# RK3399_USB2_TYPEC_USIC.net
KiCad netlist of a schematic drawn in Altium Designer
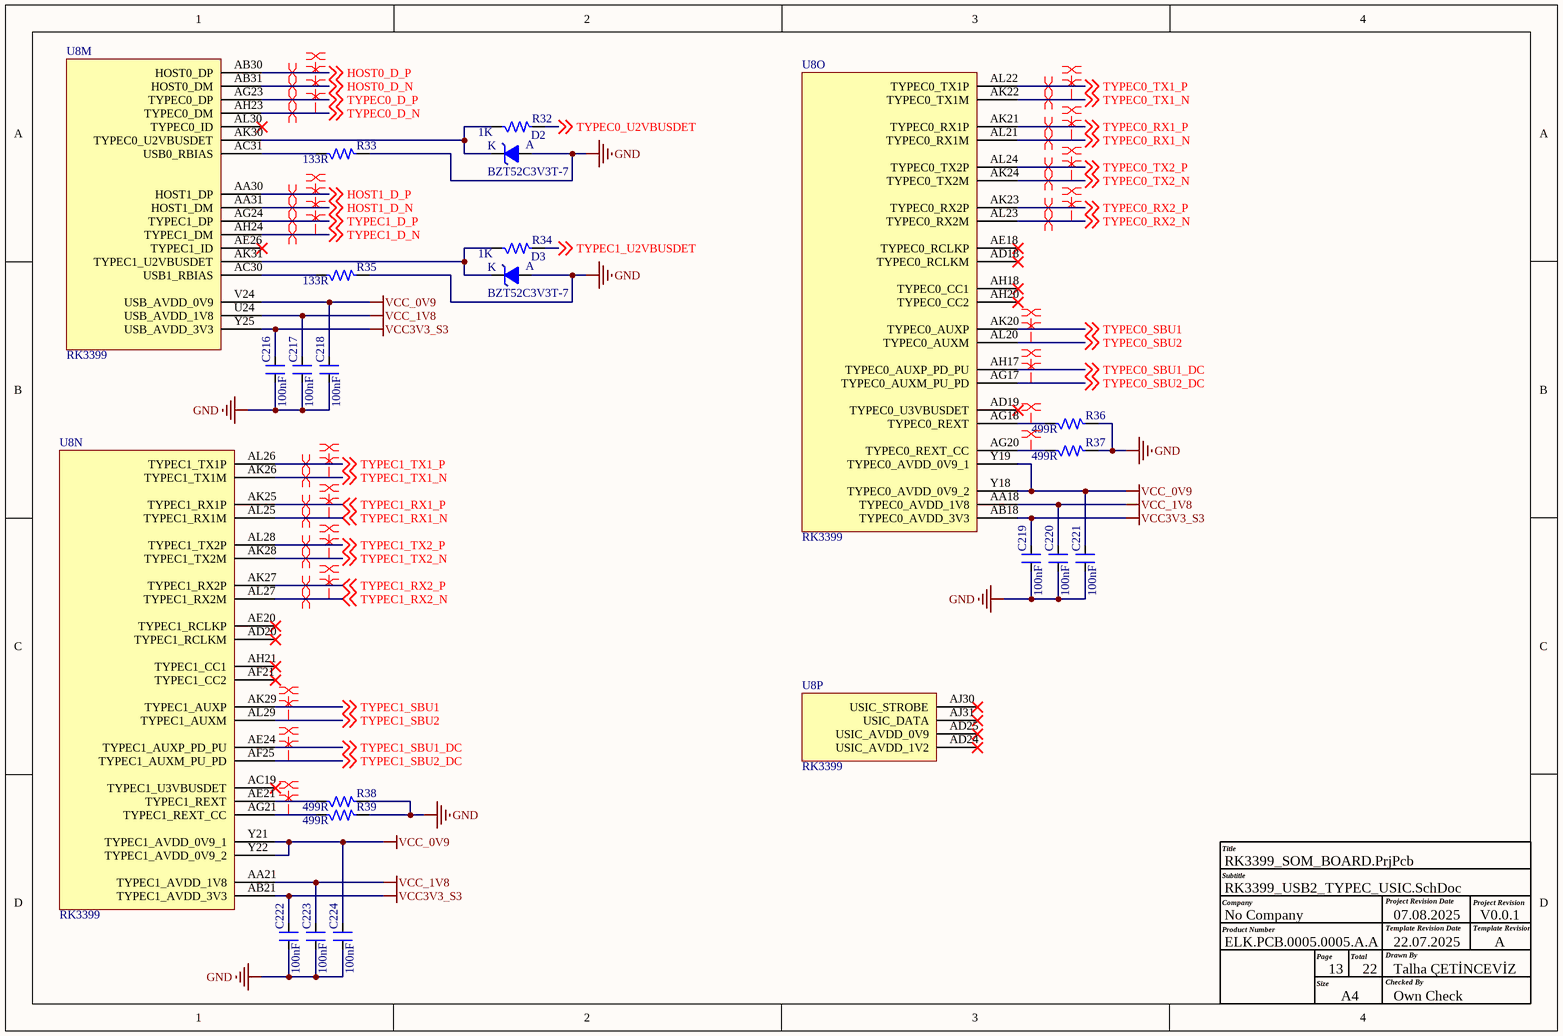
[diagram p0: RK3399_USB2_TYPEC_USIC.SchDoc]

(export (version "E")
  (design (tool "Eeschema 10.0.6"))
  (components
    (comp (ref "C216")
      (value "100nF")
      (footprint "CAP_0201")
      (description "0.1µF ±10% 25V Ceramic Capacitor X5R 0201 (0603 Metric)")
      (fields
        (field (name "MANUFACTURER") "TDK Corporation")
        (field (name "MANUFACTURER PART NUMBER") "C0603X5R1E104K030BB")
      )
      (libsource (lib "EsteemPCB_SOM_Course_intlib") (part "CAP_100nF-25V-10%-0201"))
    )
    (comp (ref "C217")
      (value "100nF")
      (footprint "CAP_0201")
      (description "0.1µF ±10% 25V Ceramic Capacitor X5R 0201 (0603 Metric)")
      (fields
        (field (name "MANUFACTURER") "TDK Corporation")
        (field (name "MANUFACTURER PART NUMBER") "C0603X5R1E104K030BB")
      )
      (libsource (lib "EsteemPCB_SOM_Course_intlib") (part "CAP_100nF-25V-10%-0201"))
    )
    (comp (ref "C218")
      (value "100nF")
      (footprint "CAP_0201")
      (description "0.1µF ±10% 25V Ceramic Capacitor X5R 0201 (0603 Metric)")
      (fields
        (field (name "MANUFACTURER") "TDK Corporation")
        (field (name "MANUFACTURER PART NUMBER") "C0603X5R1E104K030BB")
      )
      (libsource (lib "EsteemPCB_SOM_Course_intlib") (part "CAP_100nF-25V-10%-0201"))
    )
    (comp (ref "C219")
      (value "100nF")
      (footprint "CAP_0201")
      (description "0.1µF ±10% 25V Ceramic Capacitor X5R 0201 (0603 Metric)")
      (fields
        (field (name "MANUFACTURER") "TDK Corporation")
        (field (name "MANUFACTURER PART NUMBER") "C0603X5R1E104K030BB")
      )
      (libsource (lib "EsteemPCB_SOM_Course_intlib") (part "CAP_100nF-25V-10%-0201"))
    )
    (comp (ref "C220")
      (value "100nF")
      (footprint "CAP_0201")
      (description "0.1µF ±10% 25V Ceramic Capacitor X5R 0201 (0603 Metric)")
      (fields
        (field (name "MANUFACTURER") "TDK Corporation")
        (field (name "MANUFACTURER PART NUMBER") "C0603X5R1E104K030BB")
      )
      (libsource (lib "EsteemPCB_SOM_Course_intlib") (part "CAP_100nF-25V-10%-0201"))
    )
    (comp (ref "C221")
      (value "100nF")
      (footprint "CAP_0201")
      (description "0.1µF ±10% 25V Ceramic Capacitor X5R 0201 (0603 Metric)")
      (fields
        (field (name "MANUFACTURER") "TDK Corporation")
        (field (name "MANUFACTURER PART NUMBER") "C0603X5R1E104K030BB")
      )
      (libsource (lib "EsteemPCB_SOM_Course_intlib") (part "CAP_100nF-25V-10%-0201"))
    )
    (comp (ref "C222")
      (value "100nF")
      (footprint "CAP_0201")
      (description "0.1µF ±10% 25V Ceramic Capacitor X5R 0201 (0603 Metric)")
      (fields
        (field (name "MANUFACTURER") "TDK Corporation")
        (field (name "MANUFACTURER PART NUMBER") "C0603X5R1E104K030BB")
      )
      (libsource (lib "EsteemPCB_SOM_Course_intlib") (part "CAP_100nF-25V-10%-0201"))
    )
    (comp (ref "C223")
      (value "100nF")
      (footprint "CAP_0201")
      (description "0.1µF ±10% 25V Ceramic Capacitor X5R 0201 (0603 Metric)")
      (fields
        (field (name "MANUFACTURER") "TDK Corporation")
        (field (name "MANUFACTURER PART NUMBER") "C0603X5R1E104K030BB")
      )
      (libsource (lib "EsteemPCB_SOM_Course_intlib") (part "CAP_100nF-25V-10%-0201"))
    )
    (comp (ref "C224")
      (value "100nF")
      (footprint "CAP_0201")
      (description "0.1µF ±10% 25V Ceramic Capacitor X5R 0201 (0603 Metric)")
      (fields
        (field (name "MANUFACTURER") "TDK Corporation")
        (field (name "MANUFACTURER PART NUMBER") "C0603X5R1E104K030BB")
      )
      (libsource (lib "EsteemPCB_SOM_Course_intlib") (part "CAP_100nF-25V-10%-0201"))
    )
    (comp (ref "D2")
      (value "BZT52C3V3T-7")
      (footprint "DIO_SOD523")
      (description "Zener Diode 3.3V 300mW ±6% Surface Mount SOD-523")
      (fields (field (name "MANUFACTURER") "Diodes Incorporated"))
      (libsource (lib "EsteemPCB_SOM_Course_intlib") (part "DIO-Z_3.3V-300mW-SOD-523"))
    )
    (comp (ref "D3")
      (value "BZT52C3V3T-7")
      (footprint "DIO_SOD523")
      (description "Zener Diode 3.3V 300mW ±6% Surface Mount SOD-523")
      (fields (field (name "MANUFACTURER") "Diodes Incorporated"))
      (libsource (lib "EsteemPCB_SOM_Course_intlib") (part "DIO-Z_3.3V-300mW-SOD-523"))
    )
    (comp (ref "R32")
      (value "1K")
      (footprint "RES_0201")
      (description "1 kOhms ±1% 0.05W, 1/20W Chip Resistor 0201 (0603 Metric) Thick Film")
      (fields
        (field (name "MANUFACTURER") "Yageo")
        (field (name "MANUFACTURER PART NUMBER") "RC0201FR-071KL")
      )
      (libsource (lib "EsteemPCB_SOM_Course_intlib") (part "RES_1K-0.05W-1%-0201"))
    )
    (comp (ref "R33")
      (value "133R")
      (footprint "RES_0201")
      (description "133 Ohms ±1% 0.05W, 1/20W Chip Resistor 0201 (0603 Metric) Automotive AEC-Q200 Thick Film")
      (fields
        (field (name "MANUFACTURER") "Panasonic Electronic Components")
        (field (name "MANUFACTURER PART NUMBER") "ERJ-1GNF1330C")
      )
      (libsource (lib "EsteemPCB_SOM_Course_intlib") (part "RES_133R-0.05W-1%-0201"))
    )
    (comp (ref "R34")
      (value "1K")
      (footprint "RES_0201")
      (description "1 kOhms ±1% 0.05W, 1/20W Chip Resistor 0201 (0603 Metric) Thick Film")
      (fields
        (field (name "MANUFACTURER") "Yageo")
        (field (name "MANUFACTURER PART NUMBER") "RC0201FR-071KL")
      )
      (libsource (lib "EsteemPCB_SOM_Course_intlib") (part "RES_1K-0.05W-1%-0201"))
    )
    (comp (ref "R35")
      (value "133R")
      (footprint "RES_0201")
      (description "133 Ohms ±1% 0.05W, 1/20W Chip Resistor 0201 (0603 Metric) Automotive AEC-Q200 Thick Film")
      (fields
        (field (name "MANUFACTURER") "Panasonic Electronic Components")
        (field (name "MANUFACTURER PART NUMBER") "ERJ-1GNF1330C")
      )
      (libsource (lib "EsteemPCB_SOM_Course_intlib") (part "RES_133R-0.05W-1%-0201"))
    )
    (comp (ref "R36")
      (value "499R")
      (footprint "RES_0201")
      (description "499 Ohms ±1% 0.05W, 1/20W Chip Resistor 0201 (0603 Metric) Thick Film")
      (fields
        (field (name "MANUFACTURER") "Stackpole Electronics Inc")
        (field (name "MANUFACTURER PART NUMBER") "RMCF0201FT499R")
      )
      (libsource (lib "EsteemPCB_SOM_Course_intlib") (part "RES_499R-0.05W-1%-0201"))
    )
    (comp (ref "R37")
      (value "499R")
      (footprint "RES_0201")
      (description "499 Ohms ±1% 0.05W, 1/20W Chip Resistor 0201 (0603 Metric) Thick Film")
      (fields
        (field (name "MANUFACTURER") "Stackpole Electronics Inc")
        (field (name "MANUFACTURER PART NUMBER") "RMCF0201FT499R")
      )
      (libsource (lib "EsteemPCB_SOM_Course_intlib") (part "RES_499R-0.05W-1%-0201"))
    )
    (comp (ref "R38")
      (value "499R")
      (footprint "RES_0201")
      (description "499 Ohms ±1% 0.05W, 1/20W Chip Resistor 0201 (0603 Metric) Thick Film")
      (fields
        (field (name "MANUFACTURER") "Stackpole Electronics Inc")
        (field (name "MANUFACTURER PART NUMBER") "RMCF0201FT499R")
      )
      (libsource (lib "EsteemPCB_SOM_Course_intlib") (part "RES_499R-0.05W-1%-0201"))
    )
    (comp (ref "R39")
      (value "499R")
      (footprint "RES_0201")
      (description "499 Ohms ±1% 0.05W, 1/20W Chip Resistor 0201 (0603 Metric) Thick Film")
      (fields
        (field (name "MANUFACTURER") "Stackpole Electronics Inc")
        (field (name "MANUFACTURER PART NUMBER") "RMCF0201FT499R")
      )
      (libsource (lib "EsteemPCB_SOM_Course_intlib") (part "RES_499R-0.05W-1%-0201"))
    )
    (comp (ref "U8")
      (value "RK3399")
      (footprint "FBGA828_23_826X826")
      (description "RK3399 is a low power, high performance processor for computing, personal mobile.")
      (fields (field (name "MANUFACTURER") "Rockchip"))
      (libsource (lib "EsteemPCB_SOM_Course_intlib") (part "IC_RK3399-FCBGA828"))
    )
  )
  (nets
    (net (code "1") (name "GND") (class "Default")
      (node (ref "C216") (pin "1") (pinfunction "1_1") (pintype "passive"))
      (node (ref "C217") (pin "1") (pinfunction "1_1") (pintype "passive"))
      (node (ref "C218") (pin "1") (pinfunction "1_1") (pintype "passive"))
      (node (ref "C219") (pin "1") (pinfunction "1_1") (pintype "passive"))
      (node (ref "C220") (pin "1") (pinfunction "1_1") (pintype "passive"))
      (node (ref "C221") (pin "1") (pinfunction "1_1") (pintype "passive"))
      (node (ref "C222") (pin "1") (pinfunction "1_1") (pintype "passive"))
      (node (ref "C223") (pin "1") (pinfunction "1_1") (pintype "passive"))
      (node (ref "C224") (pin "1") (pinfunction "1_1") (pintype "passive"))
      (node (ref "D2") (pin "A") (pinfunction "A_A") (pintype "passive"))
      (node (ref "D3") (pin "A") (pinfunction "A_A") (pintype "passive"))
      (node (ref "R33") (pin "2") (pinfunction "2_2") (pintype "passive"))
      (node (ref "R35") (pin "2") (pinfunction "2_2") (pintype "passive"))
      (node (ref "R36") (pin "2") (pinfunction "2_2") (pintype "passive"))
      (node (ref "R37") (pin "2") (pinfunction "2_2") (pintype "passive"))
      (node (ref "R38") (pin "2") (pinfunction "2_2") (pintype "passive"))
      (node (ref "R39") (pin "2") (pinfunction "2_2") (pintype "passive"))
    )
    (net (code "2") (name "HOST0_D_N") (class "Default")
      (node (ref "U8") (pin "AB31") (pinfunction "HOST0_DM_AB31") (pintype "passive"))
    )
    (net (code "3") (name "HOST0_D_P") (class "Default")
      (node (ref "U8") (pin "AB30") (pinfunction "HOST0_DP_AB30") (pintype "passive"))
    )
    (net (code "4") (name "HOST1_D_N") (class "Default")
      (node (ref "U8") (pin "AA31") (pinfunction "HOST1_DM_AA31") (pintype "passive"))
    )
    (net (code "5") (name "HOST1_D_P") (class "Default")
      (node (ref "U8") (pin "AA30") (pinfunction "HOST1_DP_AA30") (pintype "passive"))
    )
    (net (code "6") (name "Net-(U8M-TYPEC0_U2VBUSDET)") (class "Default")
      (node (ref "D2") (pin "K") (pinfunction "K_K") (pintype "passive"))
      (node (ref "R32") (pin "1") (pinfunction "1_1") (pintype "passive"))
      (node (ref "U8") (pin "AK30") (pinfunction "TYPEC0_U2VBUSDET_AK30") (pintype "passive"))
    )
    (net (code "7") (name "Net-(U8M-TYPEC1_U2VBUSDET)") (class "Default")
      (node (ref "D3") (pin "K") (pinfunction "K_K") (pintype "passive"))
      (node (ref "R34") (pin "1") (pinfunction "1_1") (pintype "passive"))
      (node (ref "U8") (pin "AK31") (pinfunction "TYPEC1_U2VBUSDET_AK31") (pintype "passive"))
    )
    (net (code "8") (name "Net-(U8M-USB0_RBIAS)") (class "Default")
      (node (ref "R33") (pin "1") (pinfunction "1_1") (pintype "passive"))
      (node (ref "U8") (pin "AC31") (pinfunction "USB0_RBIAS_AC31") (pintype "passive"))
    )
    (net (code "9") (name "Net-(U8M-USB1_RBIAS)") (class "Default")
      (node (ref "R35") (pin "1") (pinfunction "1_1") (pintype "passive"))
      (node (ref "U8") (pin "AC30") (pinfunction "USB1_RBIAS_AC30") (pintype "passive"))
    )
    (net (code "10") (name "Net-(U8N-TYPEC1_REXT)") (class "Default")
      (node (ref "R38") (pin "1") (pinfunction "1_1") (pintype "passive"))
      (node (ref "U8") (pin "AE21") (pinfunction "TYPEC1_REXT_AE21") (pintype "passive"))
    )
    (net (code "11") (name "Net-(U8N-TYPEC1_REXT_CC)") (class "Default")
      (node (ref "R39") (pin "1") (pinfunction "1_1") (pintype "passive"))
      (node (ref "U8") (pin "AG21") (pinfunction "TYPEC1_REXT_CC_AG21") (pintype "passive"))
    )
    (net (code "12") (name "Net-(U8O-TYPEC0_REXT)") (class "Default")
      (node (ref "R36") (pin "1") (pinfunction "1_1") (pintype "passive"))
      (node (ref "U8") (pin "AG18") (pinfunction "TYPEC0_REXT_AG18") (pintype "passive"))
    )
    (net (code "13") (name "Net-(U8O-TYPEC0_REXT_CC)") (class "Default")
      (node (ref "R37") (pin "1") (pinfunction "1_1") (pintype "passive"))
      (node (ref "U8") (pin "AG20") (pinfunction "TYPEC0_REXT_CC_AG20") (pintype "passive"))
    )
    (net (code "14") (name "TYPEC0_D_N") (class "Default")
      (node (ref "U8") (pin "AH23") (pinfunction "TYPEC0_DM_AH23") (pintype "passive"))
    )
    (net (code "15") (name "TYPEC0_D_P") (class "Default")
      (node (ref "U8") (pin "AG23") (pinfunction "TYPEC0_DP_AG23") (pintype "passive"))
    )
    (net (code "16") (name "TYPEC0_RX1_N") (class "Default")
      (node (ref "U8") (pin "AL21") (pinfunction "TYPEC0_RX1M_AL21") (pintype "passive"))
    )
    (net (code "17") (name "TYPEC0_RX1_P") (class "Default")
      (node (ref "U8") (pin "AK21") (pinfunction "TYPEC0_RX1P_AK21") (pintype "passive"))
    )
    (net (code "18") (name "TYPEC0_RX2_N") (class "Default")
      (node (ref "U8") (pin "AL23") (pinfunction "TYPEC0_RX2M_AL23") (pintype "passive"))
    )
    (net (code "19") (name "TYPEC0_RX2_P") (class "Default")
      (node (ref "U8") (pin "AK23") (pinfunction "TYPEC0_RX2P_AK23") (pintype "passive"))
    )
    (net (code "20") (name "TYPEC0_SBU1") (class "Default")
      (node (ref "U8") (pin "AK20") (pinfunction "TYPEC0_AUXP_AK20") (pintype "passive"))
    )
    (net (code "21") (name "TYPEC0_SBU1_DC") (class "Default")
      (node (ref "U8") (pin "AH17") (pinfunction "TYPEC0_AUXP_PD_PU_AH17") (pintype "passive"))
    )
    (net (code "22") (name "TYPEC0_SBU2") (class "Default")
      (node (ref "U8") (pin "AL20") (pinfunction "TYPEC0_AUXM_AL20") (pintype "passive"))
    )
    (net (code "23") (name "TYPEC0_SBU2_DC") (class "Default")
      (node (ref "U8") (pin "AG17") (pinfunction "TYPEC0_AUXM_PU_PD_AG17") (pintype "passive"))
    )
    (net (code "24") (name "TYPEC0_TX1_N") (class "Default")
      (node (ref "U8") (pin "AK22") (pinfunction "TYPEC0_TX1M_AK22") (pintype "passive"))
    )
    (net (code "25") (name "TYPEC0_TX1_P") (class "Default")
      (node (ref "U8") (pin "AL22") (pinfunction "TYPEC0_TX1P_AL22") (pintype "passive"))
    )
    (net (code "26") (name "TYPEC0_TX2_N") (class "Default")
      (node (ref "U8") (pin "AK24") (pinfunction "TYPEC0_TX2M_AK24") (pintype "passive"))
    )
    (net (code "27") (name "TYPEC0_TX2_P") (class "Default")
      (node (ref "U8") (pin "AL24") (pinfunction "TYPEC0_TX2P_AL24") (pintype "passive"))
    )
    (net (code "28") (name "TYPEC0_U2VBUSDET") (class "Default")
      (node (ref "R32") (pin "2") (pinfunction "2_2") (pintype "passive"))
    )
    (net (code "29") (name "TYPEC1_D_N") (class "Default")
      (node (ref "U8") (pin "AH24") (pinfunction "TYPEC1_DM_AH24") (pintype "passive"))
    )
    (net (code "30") (name "TYPEC1_D_P") (class "Default")
      (node (ref "U8") (pin "AG24") (pinfunction "TYPEC1_DP_AG24") (pintype "passive"))
    )
    (net (code "31") (name "TYPEC1_RX1_N") (class "Default")
      (node (ref "U8") (pin "AL25") (pinfunction "TYPEC1_RX1M_AL25") (pintype "passive"))
    )
    (net (code "32") (name "TYPEC1_RX1_P") (class "Default")
      (node (ref "U8") (pin "AK25") (pinfunction "TYPEC1_RX1P_AK25") (pintype "passive"))
    )
    (net (code "33") (name "TYPEC1_RX2_N") (class "Default")
      (node (ref "U8") (pin "AL27") (pinfunction "TYPEC1_RX2M_AL27") (pintype "passive"))
    )
    (net (code "34") (name "TYPEC1_RX2_P") (class "Default")
      (node (ref "U8") (pin "AK27") (pinfunction "TYPEC1_RX2P_AK27") (pintype "passive"))
    )
    (net (code "35") (name "TYPEC1_SBU1") (class "Default")
      (node (ref "U8") (pin "AK29") (pinfunction "TYPEC1_AUXP_AK29") (pintype "passive"))
    )
    (net (code "36") (name "TYPEC1_SBU1_DC") (class "Default")
      (node (ref "U8") (pin "AE24") (pinfunction "TYPEC1_AUXP_PD_PU_AE24") (pintype "passive"))
    )
    (net (code "37") (name "TYPEC1_SBU2") (class "Default")
      (node (ref "U8") (pin "AL29") (pinfunction "TYPEC1_AUXM_AL29") (pintype "passive"))
    )
    (net (code "38") (name "TYPEC1_SBU2_DC") (class "Default")
      (node (ref "U8") (pin "AF25") (pinfunction "TYPEC1_AUXM_PU_PD_AF25") (pintype "passive"))
    )
    (net (code "39") (name "TYPEC1_TX1_N") (class "Default")
      (node (ref "U8") (pin "AK26") (pinfunction "TYPEC1_TX1M_AK26") (pintype "passive"))
    )
    (net (code "40") (name "TYPEC1_TX1_P") (class "Default")
      (node (ref "U8") (pin "AL26") (pinfunction "TYPEC1_TX1P_AL26") (pintype "passive"))
    )
    (net (code "41") (name "TYPEC1_TX2_N") (class "Default")
      (node (ref "U8") (pin "AK28") (pinfunction "TYPEC1_TX2M_AK28") (pintype "passive"))
    )
    (net (code "42") (name "TYPEC1_TX2_P") (class "Default")
      (node (ref "U8") (pin "AL28") (pinfunction "TYPEC1_TX2P_AL28") (pintype "passive"))
    )
    (net (code "43") (name "TYPEC1_U2VBUSDET") (class "Default")
      (node (ref "R34") (pin "2") (pinfunction "2_2") (pintype "passive"))
    )
    (net (code "44") (name "VCC3V3_S3") (class "Default")
      (node (ref "C216") (pin "2") (pinfunction "2_2") (pintype "passive"))
      (node (ref "C219") (pin "2") (pinfunction "2_2") (pintype "passive"))
      (node (ref "C222") (pin "2") (pinfunction "2_2") (pintype "passive"))
      (node (ref "U8") (pin "AB18") (pinfunction "TYPEC0_AVDD_3V3_AB18") (pintype "passive"))
      (node (ref "U8") (pin "AB21") (pinfunction "TYPEC1_AVDD_3V3_AB21") (pintype "passive"))
      (node (ref "U8") (pin "Y25") (pinfunction "USB_AVDD_3V3_Y25") (pintype "passive"))
    )
    (net (code "45") (name "VCC_0V9") (class "Default")
      (node (ref "C218") (pin "2") (pinfunction "2_2") (pintype "passive"))
      (node (ref "C221") (pin "2") (pinfunction "2_2") (pintype "passive"))
      (node (ref "C224") (pin "2") (pinfunction "2_2") (pintype "passive"))
      (node (ref "U8") (pin "V24") (pinfunction "USB_AVDD_0V9_V24") (pintype "passive"))
      (node (ref "U8") (pin "Y18") (pinfunction "TYPEC0_AVDD_0V9_2_Y18") (pintype "passive"))
      (node (ref "U8") (pin "Y19") (pinfunction "TYPEC0_AVDD_0V9_1_Y19") (pintype "passive"))
      (node (ref "U8") (pin "Y21") (pinfunction "TYPEC1_AVDD_0V9_1_Y21") (pintype "passive"))
      (node (ref "U8") (pin "Y22") (pinfunction "TYPEC1_AVDD_0V9_2_Y22") (pintype "passive"))
    )
    (net (code "46") (name "VCC_1V8") (class "Default")
      (node (ref "C217") (pin "2") (pinfunction "2_2") (pintype "passive"))
      (node (ref "C220") (pin "2") (pinfunction "2_2") (pintype "passive"))
      (node (ref "C223") (pin "2") (pinfunction "2_2") (pintype "passive"))
      (node (ref "U8") (pin "AA18") (pinfunction "TYPEC0_AVDD_1V8_AA18") (pintype "passive"))
      (node (ref "U8") (pin "AA21") (pinfunction "TYPEC1_AVDD_1V8_AA21") (pintype "passive"))
      (node (ref "U8") (pin "U24") (pinfunction "USB_AVDD_1V8_U24") (pintype "passive"))
    )
    (net (code "47") (name "unconnected-(U8M-TYPEC0_ID-PadAL30)") (class "Default")
      (node (ref "U8") (pin "AL30") (pinfunction "TYPEC0_ID_AL30") (pintype "passive+no_connect"))
    )
    (net (code "48") (name "unconnected-(U8M-TYPEC1_ID-PadAE26)") (class "Default")
      (node (ref "U8") (pin "AE26") (pinfunction "TYPEC1_ID_AE26") (pintype "passive+no_connect"))
    )
    (net (code "49") (name "unconnected-(U8N-TYPEC1_CC1-PadAH21)") (class "Default")
      (node (ref "U8") (pin "AH21") (pinfunction "TYPEC1_CC1_AH21") (pintype "passive+no_connect"))
    )
    (net (code "50") (name "unconnected-(U8N-TYPEC1_CC2-PadAF21)") (class "Default")
      (node (ref "U8") (pin "AF21") (pinfunction "TYPEC1_CC2_AF21") (pintype "passive+no_connect"))
    )
    (net (code "51") (name "unconnected-(U8N-TYPEC1_RCLKM-PadAD20)") (class "Default")
      (node (ref "U8") (pin "AD20") (pinfunction "TYPEC1_RCLKM_AD20") (pintype "passive+no_connect"))
    )
    (net (code "52") (name "unconnected-(U8N-TYPEC1_RCLKP-PadAE20)") (class "Default")
      (node (ref "U8") (pin "AE20") (pinfunction "TYPEC1_RCLKP_AE20") (pintype "passive+no_connect"))
    )
    (net (code "53") (name "unconnected-(U8N-TYPEC1_U3VBUSDET-PadAC19)") (class "Default")
      (node (ref "U8") (pin "AC19") (pinfunction "TYPEC1_U3VBUSDET_AC19") (pintype "passive+no_connect"))
    )
    (net (code "54") (name "unconnected-(U8O-TYPEC0_CC1-PadAH18)") (class "Default")
      (node (ref "U8") (pin "AH18") (pinfunction "TYPEC0_CC1_AH18") (pintype "passive+no_connect"))
    )
    (net (code "55") (name "unconnected-(U8O-TYPEC0_CC2-PadAH20)") (class "Default")
      (node (ref "U8") (pin "AH20") (pinfunction "TYPEC0_CC2_AH20") (pintype "passive+no_connect"))
    )
    (net (code "56") (name "unconnected-(U8O-TYPEC0_RCLKM-PadAD18)") (class "Default")
      (node (ref "U8") (pin "AD18") (pinfunction "TYPEC0_RCLKM_AD18") (pintype "passive+no_connect"))
    )
    (net (code "57") (name "unconnected-(U8O-TYPEC0_RCLKP-PadAE18)") (class "Default")
      (node (ref "U8") (pin "AE18") (pinfunction "TYPEC0_RCLKP_AE18") (pintype "passive+no_connect"))
    )
    (net (code "58") (name "unconnected-(U8O-TYPEC0_U3VBUSDET-PadAD19)") (class "Default")
      (node (ref "U8") (pin "AD19") (pinfunction "TYPEC0_U3VBUSDET_AD19") (pintype "passive+no_connect"))
    )
    (net (code "59") (name "unconnected-(U8P-USIC_AVDD_0V9-PadAD25)") (class "Default")
      (node (ref "U8") (pin "AD25") (pinfunction "USIC_AVDD_0V9_AD25") (pintype "passive+no_connect"))
    )
    (net (code "60") (name "unconnected-(U8P-USIC_AVDD_1V2-PadAD24)") (class "Default")
      (node (ref "U8") (pin "AD24") (pinfunction "USIC_AVDD_1V2_AD24") (pintype "passive+no_connect"))
    )
    (net (code "61") (name "unconnected-(U8P-USIC_DATA-PadAJ31)") (class "Default")
      (node (ref "U8") (pin "AJ31") (pinfunction "USIC_DATA_AJ31") (pintype "passive+no_connect"))
    )
    (net (code "62") (name "unconnected-(U8P-USIC_STROBE-PadAJ30)") (class "Default")
      (node (ref "U8") (pin "AJ30") (pinfunction "USIC_STROBE_AJ30") (pintype "passive+no_connect"))
    )
  )
)
